# battery.net
KiCad netlist of a schematic drawn in EAGLE
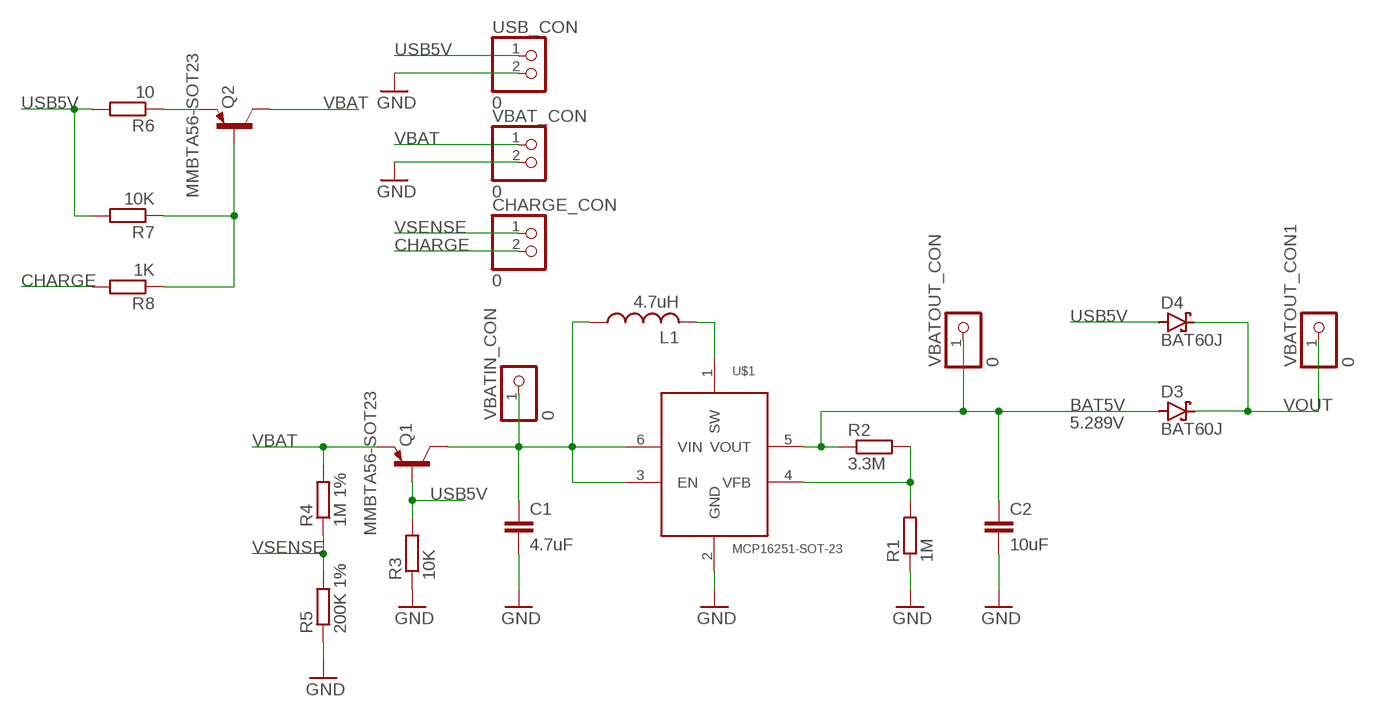
[diagram p0: schematic, sheet 1]

(export (version "E")
  (design (tool "Eeschema 10.0.6"))
  (components
    (comp (ref "C1")
      (value "4.7uF")
      (footprint "eagle-import:C0805")
      (libsource (lib "eagle-import") (part "C-EUC0805"))
    )
    (comp (ref "C2")
      (value "10uF")
      (footprint "eagle-import:C0805")
      (libsource (lib "eagle-import") (part "C-EUC0805"))
    )
    (comp (ref "CHARGE_CON")
      (value "0")
      (footprint "eagle-import:1X02")
      (libsource (lib "eagle-import") (part "PINHD-1X2"))
    )
    (comp (ref "D3")
      (value "BAT60J")
      (footprint "eagle-import:SOD323_ST")
      (libsource (lib "eagle-import") (part "BAT60J"))
    )
    (comp (ref "D4")
      (value "BAT60J")
      (footprint "eagle-import:SOD323_ST")
      (libsource (lib "eagle-import") (part "BAT60J"))
    )
    (comp (ref "L1")
      (value "4.7uH")
      (footprint "eagle-import:L4532P")
      (libsource (lib "eagle-import") (part "L-USL4532P"))
    )
    (comp (ref "Q1")
      (value "MMBTA56-SOT23")
      (footprint "eagle-import:SOT23")
      (libsource (lib "eagle-import") (part "-?SOT23MMBTA56"))
    )
    (comp (ref "Q2")
      (value "MMBTA56-SOT23")
      (footprint "eagle-import:SOT23")
      (libsource (lib "eagle-import") (part "-?SOT23MMBTA56"))
    )
    (comp (ref "R1")
      (value "1M")
      (footprint "eagle-import:R0805")
      (libsource (lib "eagle-import") (part "R-EU_R0805"))
    )
    (comp (ref "R2")
      (value "3.3M")
      (footprint "eagle-import:R0805")
      (libsource (lib "eagle-import") (part "R-EU_R0805"))
    )
    (comp (ref "R3")
      (value "10K")
      (footprint "eagle-import:R0805")
      (libsource (lib "eagle-import") (part "R-EU_R0805"))
    )
    (comp (ref "R4")
      (value "1M 1%")
      (footprint "eagle-import:R0805")
      (libsource (lib "eagle-import") (part "R-EU_R0805"))
    )
    (comp (ref "R5")
      (value "200K 1%")
      (footprint "eagle-import:R0805")
      (libsource (lib "eagle-import") (part "R-EU_R0805"))
    )
    (comp (ref "R6")
      (value "10")
      (footprint "eagle-import:R0805")
      (libsource (lib "eagle-import") (part "R-EU_R0805"))
    )
    (comp (ref "R7")
      (value "10K")
      (footprint "eagle-import:R0805")
      (libsource (lib "eagle-import") (part "R-EU_R0805"))
    )
    (comp (ref "R8")
      (value "1K")
      (footprint "eagle-import:R0805")
      (libsource (lib "eagle-import") (part "R-EU_R0805"))
    )
    (comp (ref "U$1")
      (value "MCP16251-SOT-23")
      (footprint "eagle-import:SOT-23")
      (libsource (lib "eagle-import") (part "MCP16251-SOT-23"))
    )
    (comp (ref "USB_CON")
      (value "0")
      (footprint "eagle-import:1X02")
      (libsource (lib "eagle-import") (part "PINHD-1X2"))
    )
    (comp (ref "VBATIN_CON")
      (value "0")
      (footprint "eagle-import:1X01")
      (libsource (lib "eagle-import") (part "PINHD-1X1"))
    )
    (comp (ref "VBATOUT_CON")
      (value "0")
      (footprint "eagle-import:1X01")
      (libsource (lib "eagle-import") (part "PINHD-1X1"))
    )
    (comp (ref "VBATOUT_CON1")
      (value "0")
      (footprint "eagle-import:1X01")
      (libsource (lib "eagle-import") (part "PINHD-1X1"))
    )
    (comp (ref "VBAT_CON")
      (value "0")
      (footprint "eagle-import:1X02")
      (libsource (lib "eagle-import") (part "PINHD-1X2"))
    )
  )
  (nets
    (net (code "1") (name "/BAT5V") (class "Default")
      (node (ref "C2") (pin "1") (pinfunction "1_1") (pintype "passive"))
      (node (ref "D3") (pin "A") (pinfunction "A_A") (pintype "passive"))
      (node (ref "R2") (pin "1") (pinfunction "1_1") (pintype "passive"))
      (node (ref "U$1") (pin "5") (pinfunction "VOUT_5") (pintype "bidirectional"))
      (node (ref "VBATOUT_CON") (pin "1") (pinfunction "1_1") (pintype "passive"))
    )
    (net (code "2") (name "/CHARGE") (class "Default")
      (node (ref "CHARGE_CON") (pin "2") (pinfunction "2_2") (pintype "passive"))
      (node (ref "R8") (pin "2") (pinfunction "2_2") (pintype "passive"))
    )
    (net (code "3") (name "/USB5V") (class "Default")
      (node (ref "D4") (pin "A") (pinfunction "A_A") (pintype "passive"))
      (node (ref "Q1") (pin "1") (pinfunction "B_1") (pintype "passive"))
      (node (ref "R3") (pin "2") (pinfunction "2_2") (pintype "passive"))
      (node (ref "R6") (pin "2") (pinfunction "2_2") (pintype "passive"))
      (node (ref "R7") (pin "2") (pinfunction "2_2") (pintype "passive"))
      (node (ref "USB_CON") (pin "1") (pinfunction "1_1") (pintype "passive"))
    )
    (net (code "4") (name "/VBAT") (class "Default")
      (node (ref "Q1") (pin "2") (pinfunction "E_2") (pintype "passive"))
      (node (ref "Q2") (pin "3") (pinfunction "C_3") (pintype "passive"))
      (node (ref "R4") (pin "2") (pinfunction "2_2") (pintype "passive"))
      (node (ref "VBAT_CON") (pin "1") (pinfunction "1_1") (pintype "passive"))
    )
    (net (code "5") (name "/VOUT") (class "Default")
      (node (ref "D3") (pin "C") (pinfunction "C_C") (pintype "passive"))
      (node (ref "D4") (pin "C") (pinfunction "C_C") (pintype "passive"))
      (node (ref "VBATOUT_CON1") (pin "1") (pinfunction "1_1") (pintype "passive"))
    )
    (net (code "6") (name "/VSENSE") (class "Default")
      (node (ref "CHARGE_CON") (pin "1") (pinfunction "1_1") (pintype "passive"))
      (node (ref "R4") (pin "1") (pinfunction "1_1") (pintype "passive"))
      (node (ref "R5") (pin "2") (pinfunction "2_2") (pintype "passive"))
    )
    (net (code "7") (name "GND") (class "Default")
      (node (ref "C1") (pin "2") (pinfunction "2_2") (pintype "passive"))
      (node (ref "C2") (pin "2") (pinfunction "2_2") (pintype "passive"))
      (node (ref "R1") (pin "1") (pinfunction "1_1") (pintype "passive"))
      (node (ref "R3") (pin "1") (pinfunction "1_1") (pintype "passive"))
      (node (ref "R5") (pin "1") (pinfunction "1_1") (pintype "passive"))
      (node (ref "U$1") (pin "2") (pinfunction "GND_2") (pintype "bidirectional"))
      (node (ref "USB_CON") (pin "2") (pinfunction "2_2") (pintype "passive"))
      (node (ref "VBAT_CON") (pin "2") (pinfunction "2_2") (pintype "passive"))
    )
    (net (code "8") (name "Net-(Q1-C)") (class "Default")
      (node (ref "C1") (pin "1") (pinfunction "1_1") (pintype "passive"))
      (node (ref "L1") (pin "1") (pinfunction "1_1") (pintype "passive"))
      (node (ref "Q1") (pin "3") (pinfunction "C_3") (pintype "passive"))
      (node (ref "U$1") (pin "3") (pinfunction "EN_3") (pintype "bidirectional"))
      (node (ref "U$1") (pin "6") (pinfunction "VIN_6") (pintype "bidirectional"))
      (node (ref "VBATIN_CON") (pin "1") (pinfunction "1_1") (pintype "passive"))
    )
    (net (code "9") (name "Net-(Q2-B)") (class "Default")
      (node (ref "Q2") (pin "1") (pinfunction "B_1") (pintype "passive"))
      (node (ref "R7") (pin "1") (pinfunction "1_1") (pintype "passive"))
      (node (ref "R8") (pin "1") (pinfunction "1_1") (pintype "passive"))
    )
    (net (code "10") (name "Net-(Q2-E)") (class "Default")
      (node (ref "Q2") (pin "2") (pinfunction "E_2") (pintype "passive"))
      (node (ref "R6") (pin "1") (pinfunction "1_1") (pintype "passive"))
    )
    (net (code "11") (name "Net-(U$1-SW)") (class "Default")
      (node (ref "L1") (pin "2") (pinfunction "2_2") (pintype "passive"))
      (node (ref "U$1") (pin "1") (pinfunction "SW_1") (pintype "bidirectional"))
    )
    (net (code "12") (name "Net-(U$1-VFB)") (class "Default")
      (node (ref "R1") (pin "2") (pinfunction "2_2") (pintype "passive"))
      (node (ref "R2") (pin "2") (pinfunction "2_2") (pintype "passive"))
      (node (ref "U$1") (pin "4") (pinfunction "VFB_4") (pintype "bidirectional"))
    )
  )
)
